# ME433_PCB.net
KiCad netlist of a schematic drawn in EAGLE
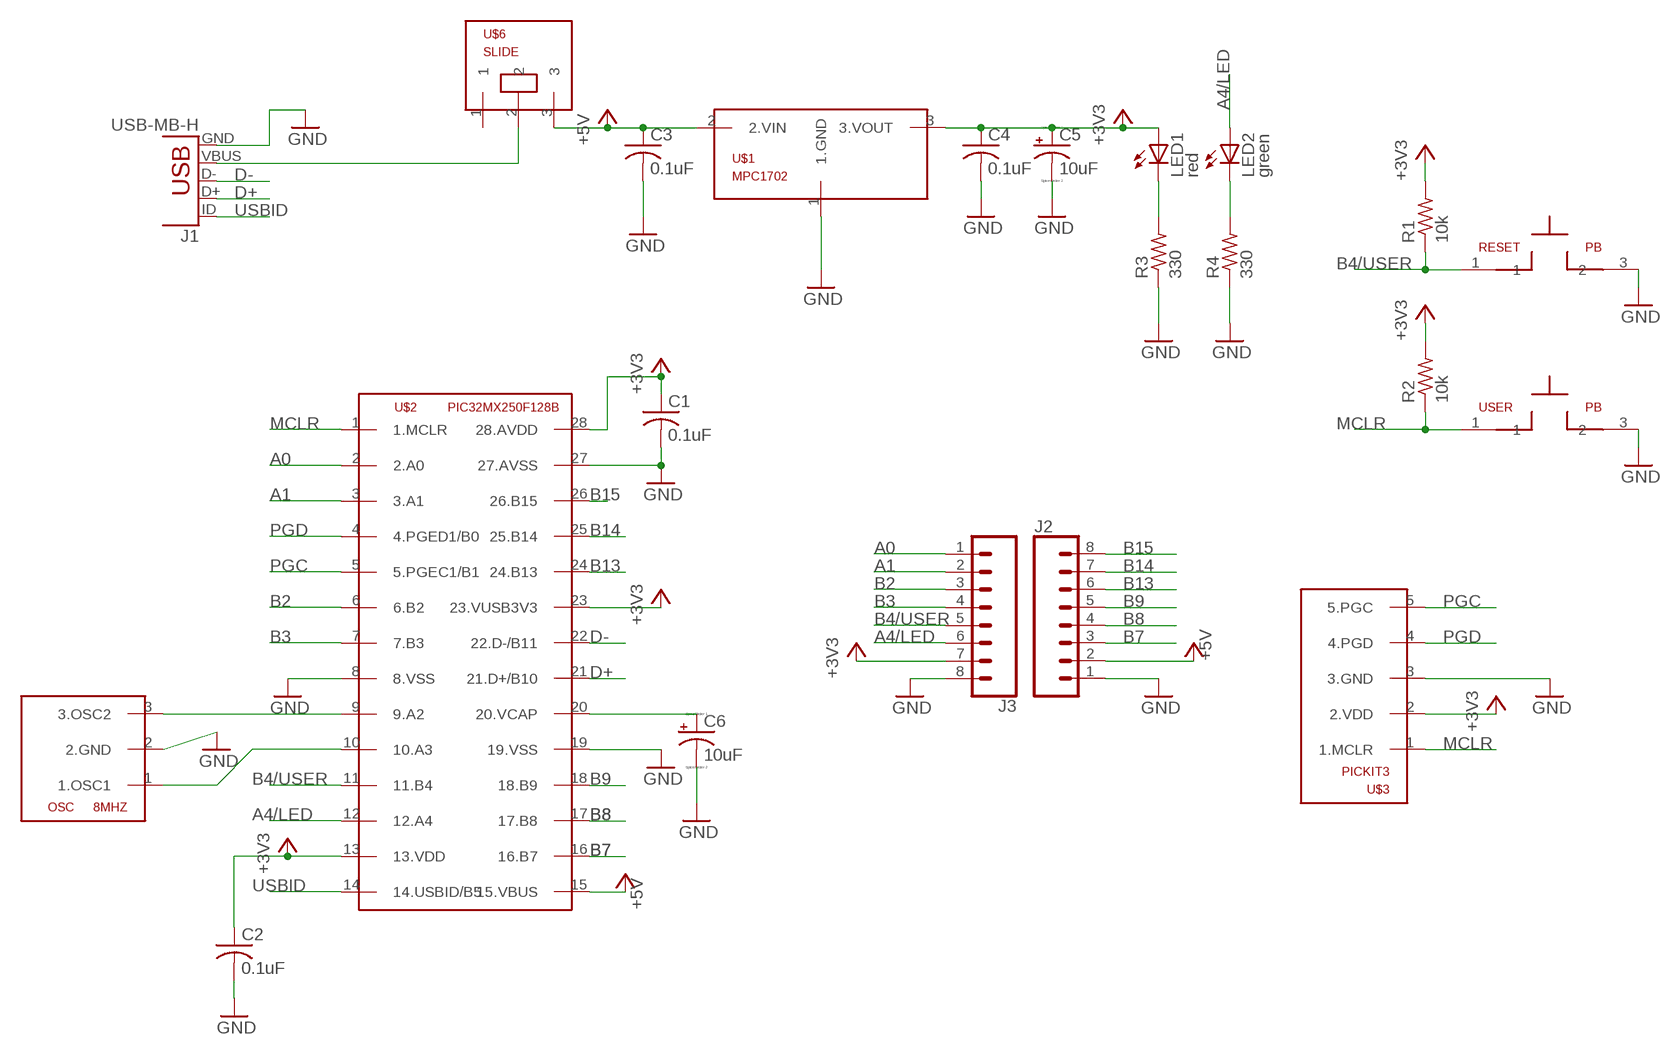
[diagram p0: schematic, sheet 1]

(export (version "E")
  (design (tool "Eeschema 10.0.6"))
  (components
    (comp (ref "8MHZ")
      (value "OSC")
      (footprint "eagle-import:OSC")
      (libsource (lib "eagle-import") (part "OSC"))
    )
    (comp (ref "C1")
      (value "0.1uF")
      (footprint "eagle-import:C025-025X050")
      (libsource (lib "eagle-import") (part "C-US025-025X050"))
    )
    (comp (ref "C2")
      (value "0.1uF")
      (footprint "eagle-import:C025-025X050")
      (libsource (lib "eagle-import") (part "C-US025-025X050"))
    )
    (comp (ref "C3")
      (value "0.1uF")
      (footprint "eagle-import:C025-025X050")
      (libsource (lib "eagle-import") (part "C-US025-025X050"))
    )
    (comp (ref "C4")
      (value "0.1uF")
      (footprint "eagle-import:C025-025X050")
      (libsource (lib "eagle-import") (part "C-US025-025X050"))
    )
    (comp (ref "C5")
      (value "10uF")
      (footprint "eagle-import:B45181B")
      (libsource (lib "eagle-import") (part "CPOL-USB45181B"))
    )
    (comp (ref "C6")
      (value "10uF")
      (footprint "eagle-import:B45181B")
      (libsource (lib "eagle-import") (part "CPOL-USB45181B"))
    )
    (comp (ref "J1")
      (value "USB-MB-H")
      (footprint "eagle-import:USB-MB-H")
      (libsource (lib "eagle-import") (part "USB-MB-H"))
    )
    (comp (ref "J2")
      (value "CONN_08\"")
      (footprint "eagle-import:1X08")
      (libsource (lib "eagle-import") (part "CONN_08{dblquote}"))
    )
    (comp (ref "J3")
      (value "CONN_08\"")
      (footprint "eagle-import:1X08")
      (libsource (lib "eagle-import") (part "CONN_08{dblquote}"))
    )
    (comp (ref "LED1")
      (value "red")
      (footprint "eagle-import:LED3MM")
      (libsource (lib "eagle-import") (part "LED3MM"))
    )
    (comp (ref "LED2")
      (value "green")
      (footprint "eagle-import:LED3MM")
      (libsource (lib "eagle-import") (part "LED3MM"))
    )
    (comp (ref "R1")
      (value "10k")
      (footprint "eagle-import:0207_10")
      (libsource (lib "eagle-import") (part "R-US_0207/10"))
    )
    (comp (ref "R2")
      (value "10k")
      (footprint "eagle-import:0207_10")
      (libsource (lib "eagle-import") (part "R-US_0207/10"))
    )
    (comp (ref "R3")
      (value "330")
      (footprint "eagle-import:0207_10")
      (libsource (lib "eagle-import") (part "R-US_0207/10"))
    )
    (comp (ref "R4")
      (value "330")
      (footprint "eagle-import:0207_10")
      (libsource (lib "eagle-import") (part "R-US_0207/10"))
    )
    (comp (ref "RESET")
      (value "PB")
      (footprint "eagle-import:PB")
      (libsource (lib "eagle-import") (part "PB"))
    )
    (comp (ref "U$1")
      (value "MPC1702")
      (footprint "eagle-import:TO92")
      (libsource (lib "eagle-import") (part "MPC1702"))
    )
    (comp (ref "U$2")
      (value "PIC32MX250F128B")
      (footprint "eagle-import:DIL28-3")
      (libsource (lib "eagle-import") (part "PIC32MX250F128B"))
    )
    (comp (ref "U$3")
      (value "PICKIT3")
      (footprint "eagle-import:1X05")
      (libsource (lib "eagle-import") (part "PICKIT3"))
    )
    (comp (ref "U$6")
      (value "SLIDE")
      (footprint "eagle-import:SLIDE")
      (libsource (lib "eagle-import") (part "SLIDE"))
    )
    (comp (ref "USER")
      (value "PB")
      (footprint "eagle-import:PB")
      (libsource (lib "eagle-import") (part "PB"))
    )
  )
  (nets
    (net (code "1") (name "+3V3") (class "Default")
      (node (ref "C1") (pin "1") (pinfunction "1_1") (pintype "passive"))
      (node (ref "C2") (pin "1") (pinfunction "1_1") (pintype "passive"))
      (node (ref "C4") (pin "1") (pinfunction "1_1") (pintype "passive"))
      (node (ref "C5") (pin "+") (pinfunction "+_+") (pintype "passive"))
      (node (ref "J3") (pin "7") (pinfunction "7_7") (pintype "passive"))
      (node (ref "LED1") (pin "A") (pinfunction "A_A") (pintype "passive"))
      (node (ref "R1") (pin "2") (pinfunction "2_2") (pintype "passive"))
      (node (ref "R2") (pin "2") (pinfunction "2_2") (pintype "passive"))
      (node (ref "U$1") (pin "3") (pinfunction "3.VOUT_3") (pintype "bidirectional"))
      (node (ref "U$2") (pin "13") (pinfunction "13.VDD_13") (pintype "bidirectional"))
      (node (ref "U$2") (pin "23") (pinfunction "23.VUSB3V3_23") (pintype "bidirectional"))
      (node (ref "U$2") (pin "28") (pinfunction "28.AVDD_28") (pintype "bidirectional"))
      (node (ref "U$3") (pin "2") (pinfunction "2.VDD_2") (pintype "bidirectional"))
    )
    (net (code "2") (name "+5V") (class "Default")
      (node (ref "C3") (pin "1") (pinfunction "1_1") (pintype "passive"))
      (node (ref "J2") (pin "2") (pinfunction "2_2") (pintype "passive"))
      (node (ref "U$1") (pin "2") (pinfunction "2.VIN_2") (pintype "bidirectional"))
      (node (ref "U$2") (pin "15") (pinfunction "15.VBUS_15") (pintype "bidirectional"))
      (node (ref "U$6") (pin "3") (pinfunction "3_3") (pintype "bidirectional"))
    )
    (net (code "3") (name "/A0") (class "Default")
      (node (ref "J3") (pin "1") (pinfunction "1_1") (pintype "passive"))
      (node (ref "U$2") (pin "2") (pinfunction "2.A0_2") (pintype "bidirectional"))
    )
    (net (code "4") (name "/A1") (class "Default")
      (node (ref "J3") (pin "2") (pinfunction "2_2") (pintype "passive"))
      (node (ref "U$2") (pin "3") (pinfunction "3.A1_3") (pintype "bidirectional"))
    )
    (net (code "5") (name "/A4{slash}LED") (class "Default")
      (node (ref "J3") (pin "6") (pinfunction "6_6") (pintype "passive"))
      (node (ref "LED2") (pin "A") (pinfunction "A_A") (pintype "passive"))
      (node (ref "U$2") (pin "12") (pinfunction "12.A4_12") (pintype "bidirectional"))
    )
    (net (code "6") (name "/B2") (class "Default")
      (node (ref "J3") (pin "3") (pinfunction "3_3") (pintype "passive"))
      (node (ref "U$2") (pin "6") (pinfunction "6.B2_6") (pintype "bidirectional"))
    )
    (net (code "7") (name "/B3") (class "Default")
      (node (ref "J3") (pin "4") (pinfunction "4_4") (pintype "passive"))
      (node (ref "U$2") (pin "7") (pinfunction "7.B3_7") (pintype "bidirectional"))
    )
    (net (code "8") (name "/B4{slash}USER") (class "Default")
      (node (ref "J3") (pin "5") (pinfunction "5_5") (pintype "passive"))
      (node (ref "R1") (pin "1") (pinfunction "1_1") (pintype "passive"))
      (node (ref "RESET") (pin "1") (pinfunction "1_1") (pintype "bidirectional"))
      (node (ref "U$2") (pin "11") (pinfunction "11.B4_11") (pintype "bidirectional"))
    )
    (net (code "9") (name "/B7") (class "Default")
      (node (ref "J2") (pin "3") (pinfunction "3_3") (pintype "passive"))
      (node (ref "U$2") (pin "16") (pinfunction "16.B7_16") (pintype "bidirectional"))
    )
    (net (code "10") (name "/B8") (class "Default")
      (node (ref "J2") (pin "4") (pinfunction "4_4") (pintype "passive"))
      (node (ref "U$2") (pin "17") (pinfunction "17.B8_17") (pintype "bidirectional"))
    )
    (net (code "11") (name "/B9") (class "Default")
      (node (ref "J2") (pin "5") (pinfunction "5_5") (pintype "passive"))
      (node (ref "U$2") (pin "18") (pinfunction "18.B9_18") (pintype "bidirectional"))
    )
    (net (code "12") (name "/B13") (class "Default")
      (node (ref "J2") (pin "6") (pinfunction "6_6") (pintype "passive"))
      (node (ref "U$2") (pin "24") (pinfunction "24.B13_24") (pintype "bidirectional"))
    )
    (net (code "13") (name "/B14") (class "Default")
      (node (ref "J2") (pin "7") (pinfunction "7_7") (pintype "passive"))
      (node (ref "U$2") (pin "25") (pinfunction "25.B14_25") (pintype "bidirectional"))
    )
    (net (code "14") (name "/B15") (class "Default")
      (node (ref "J2") (pin "8") (pinfunction "8_8") (pintype "passive"))
      (node (ref "U$2") (pin "26") (pinfunction "26.B15_26") (pintype "bidirectional"))
    )
    (net (code "15") (name "/D+") (class "Default")
      (node (ref "J1") (pin "D+") (pinfunction "D+_D+") (pintype "bidirectional"))
      (node (ref "U$2") (pin "21") (pinfunction "21.D+/B10_21") (pintype "bidirectional"))
    )
    (net (code "16") (name "/D-") (class "Default")
      (node (ref "J1") (pin "D-") (pinfunction "D-_D-") (pintype "bidirectional"))
      (node (ref "U$2") (pin "22") (pinfunction "22.D-/B11_22") (pintype "bidirectional"))
    )
    (net (code "17") (name "/MCLR") (class "Default")
      (node (ref "R2") (pin "1") (pinfunction "1_1") (pintype "passive"))
      (node (ref "U$2") (pin "1") (pinfunction "1.MCLR_1") (pintype "bidirectional"))
      (node (ref "U$3") (pin "1") (pinfunction "1.MCLR_1") (pintype "bidirectional"))
      (node (ref "USER") (pin "1") (pinfunction "1_1") (pintype "bidirectional"))
    )
    (net (code "18") (name "/PGC") (class "Default")
      (node (ref "U$2") (pin "5") (pinfunction "5.PGEC1/B1_5") (pintype "bidirectional"))
      (node (ref "U$3") (pin "5") (pinfunction "5.PGC_5") (pintype "bidirectional"))
    )
    (net (code "19") (name "/PGD") (class "Default")
      (node (ref "U$2") (pin "4") (pinfunction "4.PGED1/B0_4") (pintype "bidirectional"))
      (node (ref "U$3") (pin "4") (pinfunction "4.PGD_4") (pintype "bidirectional"))
    )
    (net (code "20") (name "/USBID") (class "Default")
      (node (ref "J1") (pin "ID") (pinfunction "ID_ID") (pintype "bidirectional"))
      (node (ref "U$2") (pin "14") (pinfunction "14.USBID/B5_14") (pintype "bidirectional"))
    )
    (net (code "21") (name "GND") (class "Default")
      (node (ref "8MHZ") (pin "2") (pinfunction "2.GND_2") (pintype "bidirectional"))
      (node (ref "C1") (pin "2") (pinfunction "2_2") (pintype "passive"))
      (node (ref "C2") (pin "2") (pinfunction "2_2") (pintype "passive"))
      (node (ref "C3") (pin "2") (pinfunction "2_2") (pintype "passive"))
      (node (ref "C4") (pin "2") (pinfunction "2_2") (pintype "passive"))
      (node (ref "C5") (pin "-") (pinfunction "-_-") (pintype "passive"))
      (node (ref "C6") (pin "-") (pinfunction "-_-") (pintype "passive"))
      (node (ref "J1") (pin "GND") (pinfunction "GND_GND") (pintype "bidirectional"))
      (node (ref "J2") (pin "1") (pinfunction "1_1") (pintype "passive"))
      (node (ref "J3") (pin "8") (pinfunction "8_8") (pintype "passive"))
      (node (ref "R3") (pin "1") (pinfunction "1_1") (pintype "passive"))
      (node (ref "R4") (pin "1") (pinfunction "1_1") (pintype "passive"))
      (node (ref "RESET") (pin "3") (pinfunction "2_3") (pintype "bidirectional"))
      (node (ref "U$1") (pin "1") (pinfunction "1.GND_1") (pintype "bidirectional"))
      (node (ref "U$2") (pin "19") (pinfunction "19.VSS_19") (pintype "bidirectional"))
      (node (ref "U$2") (pin "27") (pinfunction "27.AVSS_27") (pintype "bidirectional"))
      (node (ref "U$2") (pin "8") (pinfunction "8.VSS_8") (pintype "bidirectional"))
      (node (ref "U$3") (pin "3") (pinfunction "3.GND_3") (pintype "bidirectional"))
      (node (ref "USER") (pin "3") (pinfunction "2_3") (pintype "bidirectional"))
    )
    (net (code "22") (name "Net-(8MHZ-1.OSC1)") (class "Default")
      (node (ref "8MHZ") (pin "1") (pinfunction "1.OSC1_1") (pintype "bidirectional"))
      (node (ref "U$2") (pin "10") (pinfunction "10.A3_10") (pintype "bidirectional"))
    )
    (net (code "23") (name "Net-(8MHZ-3.OSC2)") (class "Default")
      (node (ref "8MHZ") (pin "3") (pinfunction "3.OSC2_3") (pintype "bidirectional"))
      (node (ref "U$2") (pin "9") (pinfunction "9.A2_9") (pintype "bidirectional"))
    )
    (net (code "24") (name "Net-(J1-PadVBUS)") (class "Default")
      (node (ref "J1") (pin "VBUS") (pinfunction "VBUS_VBUS") (pintype "bidirectional"))
      (node (ref "U$6") (pin "2") (pinfunction "2_2") (pintype "bidirectional"))
    )
    (net (code "25") (name "Net-(LED1-C)") (class "Default")
      (node (ref "LED1") (pin "K") (pinfunction "C_K") (pintype "passive"))
      (node (ref "R3") (pin "2") (pinfunction "2_2") (pintype "passive"))
    )
    (net (code "26") (name "Net-(LED2-C)") (class "Default")
      (node (ref "LED2") (pin "K") (pinfunction "C_K") (pintype "passive"))
      (node (ref "R4") (pin "2") (pinfunction "2_2") (pintype "passive"))
    )
    (net (code "27") (name "Net-(U$2-20.VCAP)") (class "Default")
      (node (ref "C6") (pin "+") (pinfunction "+_+") (pintype "passive"))
      (node (ref "U$2") (pin "20") (pinfunction "20.VCAP_20") (pintype "bidirectional"))
    )
    (net (code "28") (name "unconnected-(U$6-Pad1)") (class "Default")
      (node (ref "U$6") (pin "1") (pinfunction "1_1") (pintype "bidirectional"))
    )
  )
)
